# ftduino.net
KiCad netlist of a schematic drawn in EAGLE
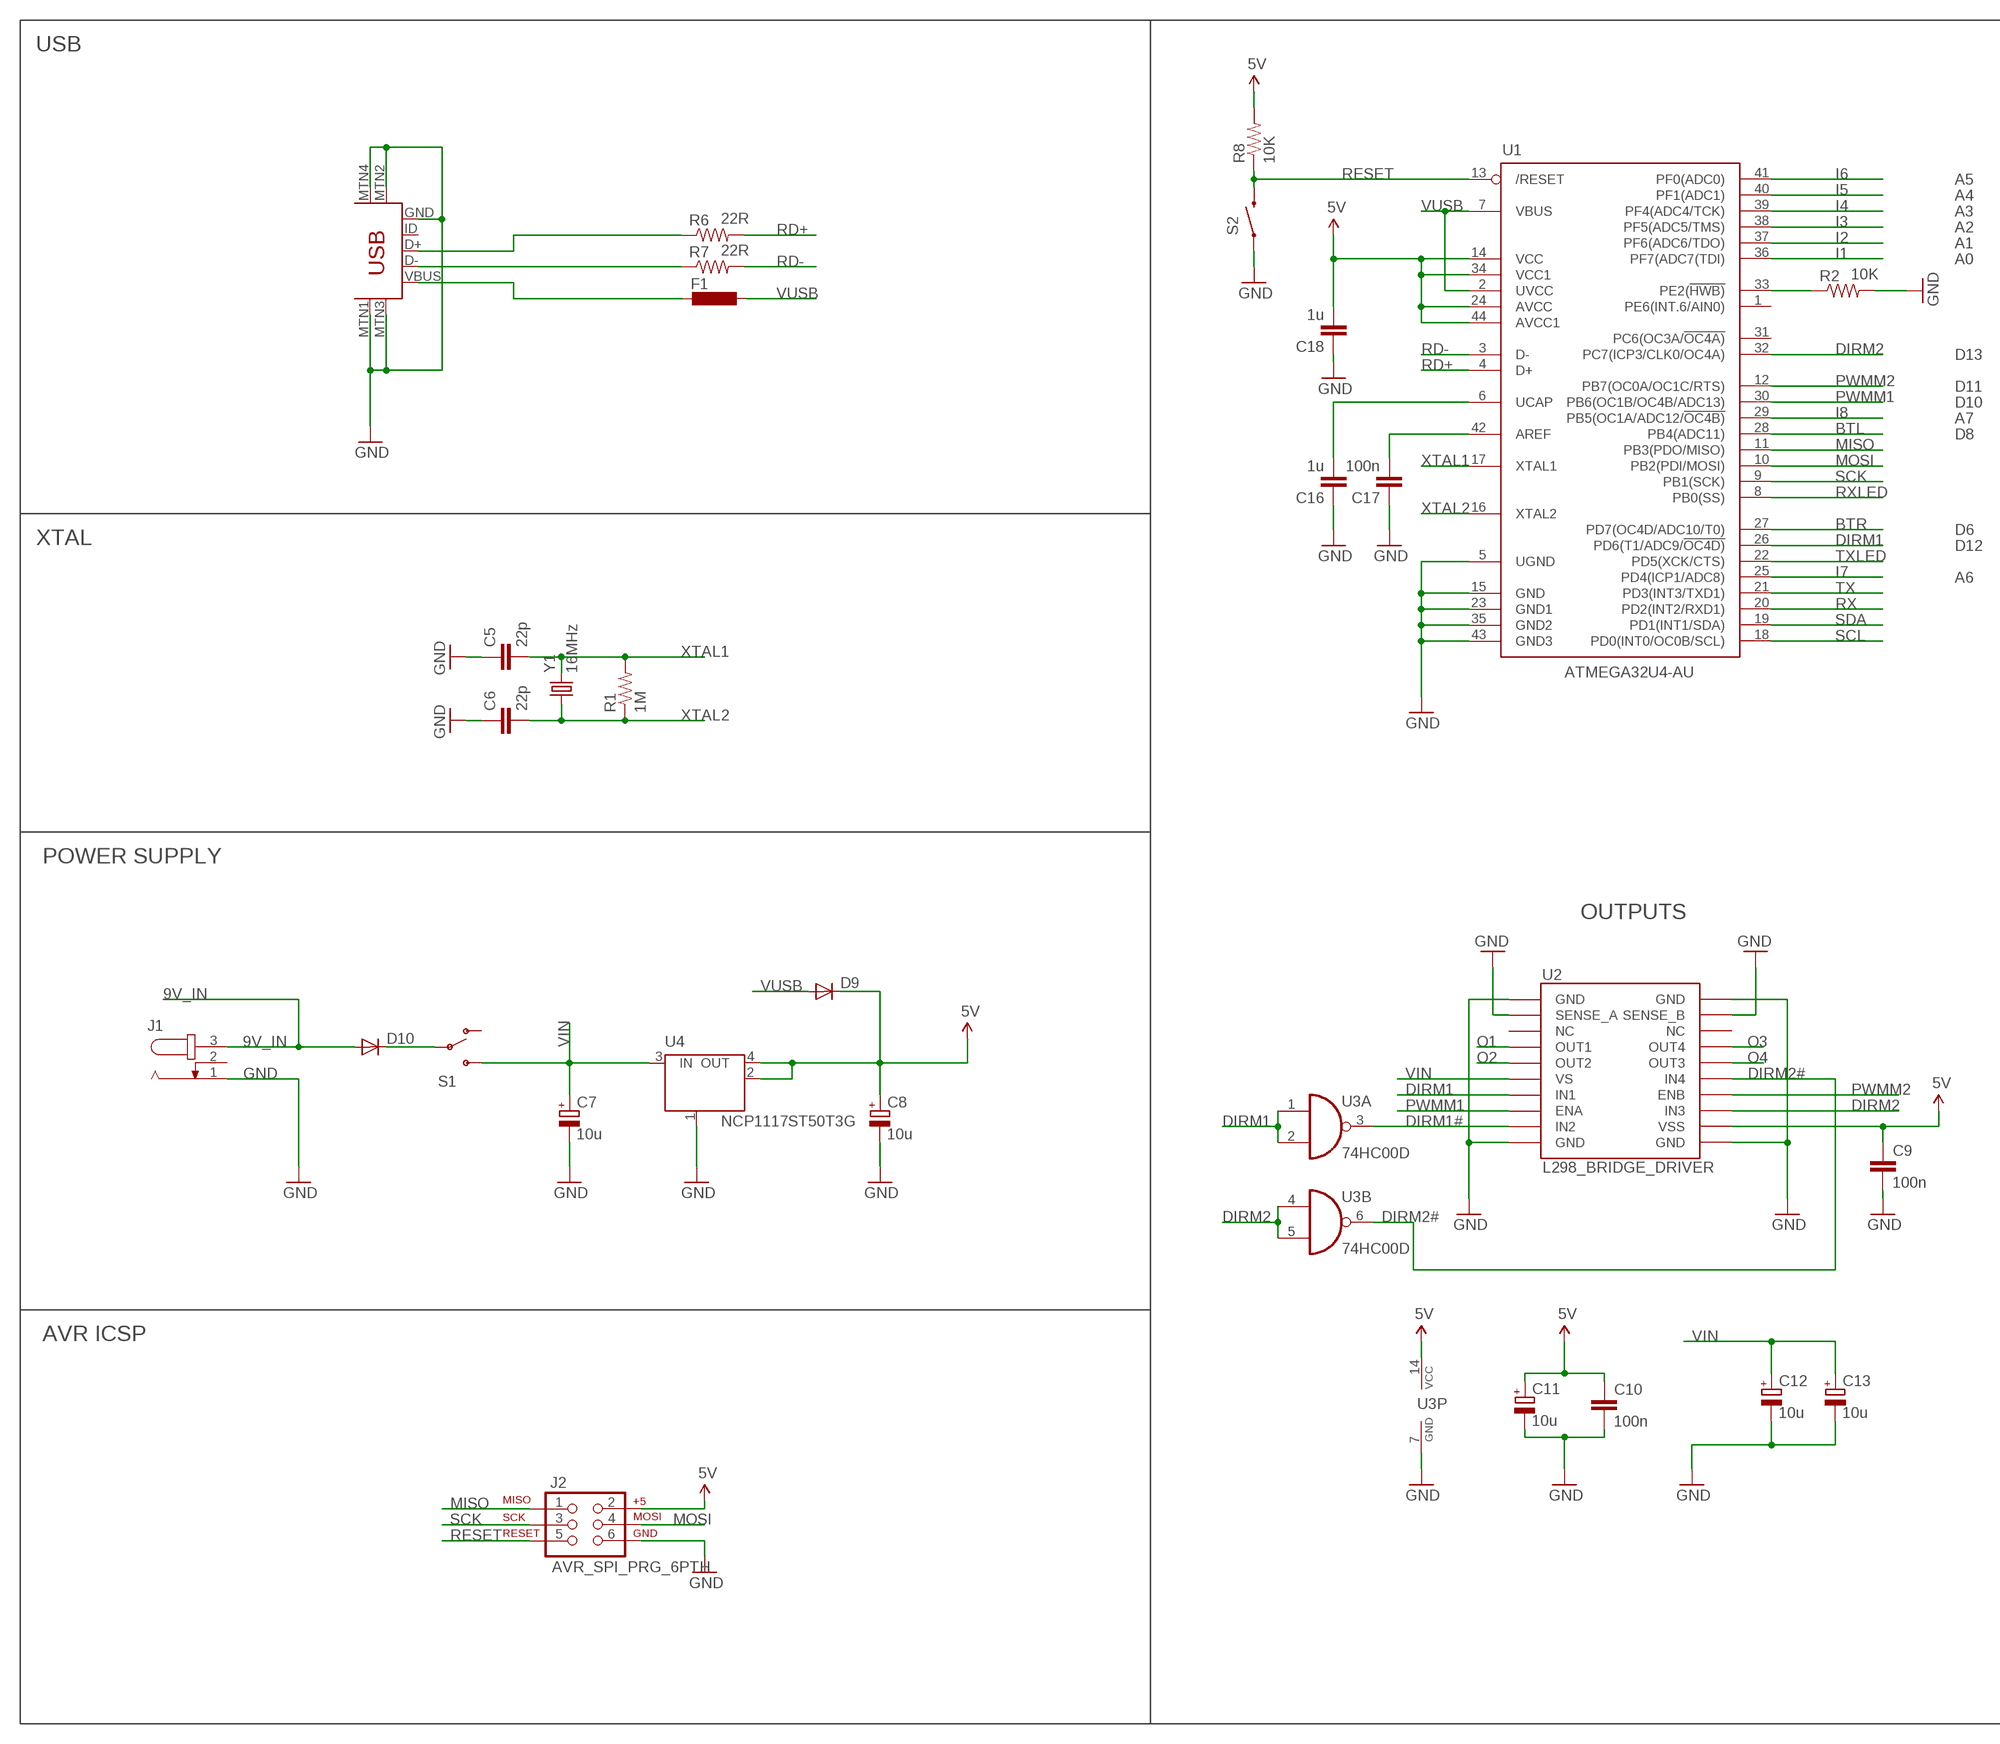
[diagram p0: schematic, sheet 1, part 1 of 2]
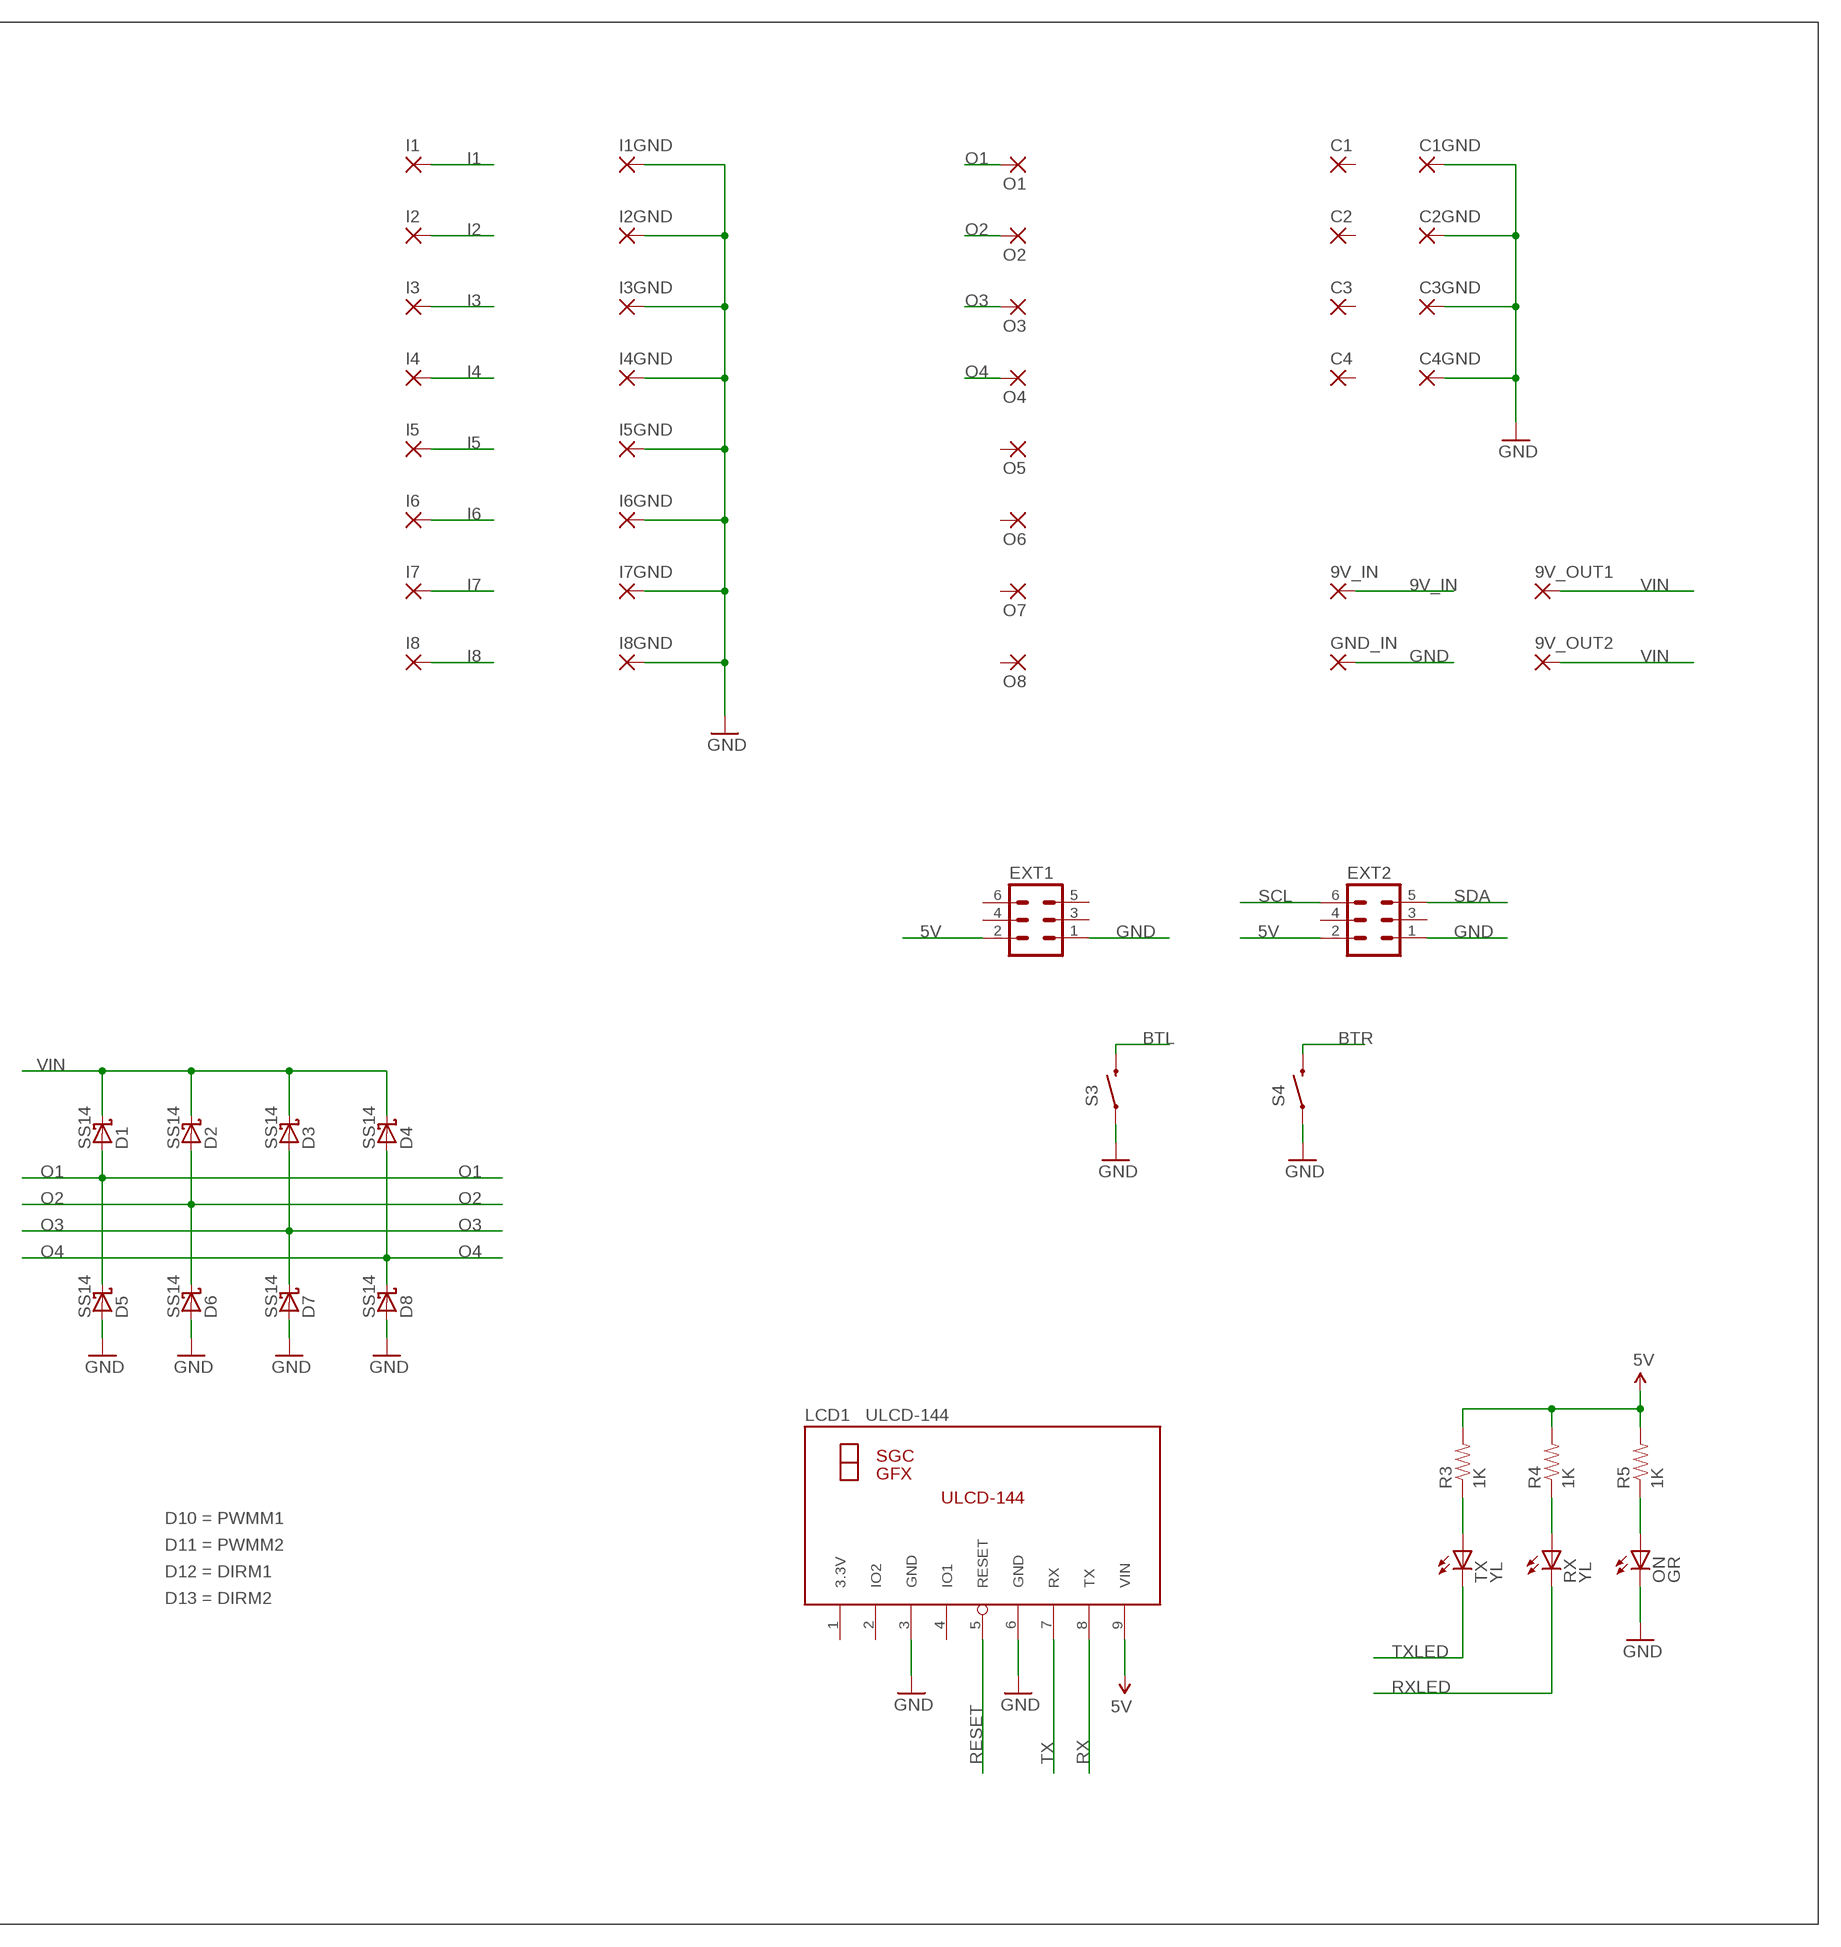
[diagram p1: schematic, sheet 1, part 2 of 2]

(export (version "E")
  (design (tool "Eeschema 10.0.6"))
  (components
    (comp (ref "9V_IN")
      (value "5,0/3,2")
      (footprint "eagle-import:5,0_3,2")
      (libsource (lib "eagle-import") (part "5,0/3,2"))
    )
    (comp (ref "9V_OUT1")
      (value "5,0/3,2")
      (footprint "eagle-import:5,0_3,2")
      (libsource (lib "eagle-import") (part "5,0/3,2"))
    )
    (comp (ref "9V_OUT2")
      (value "5,0/3,2")
      (footprint "eagle-import:5,0_3,2")
      (libsource (lib "eagle-import") (part "5,0/3,2"))
    )
    (comp (ref "C1")
      (value "5,0/3,2")
      (footprint "eagle-import:5,0_3,2")
      (libsource (lib "eagle-import") (part "5,0/3,2"))
    )
    (comp (ref "C1GND")
      (value "5,0/3,2")
      (footprint "eagle-import:5,0_3,2")
      (libsource (lib "eagle-import") (part "5,0/3,2"))
    )
    (comp (ref "C2")
      (value "5,0/3,2")
      (footprint "eagle-import:5,0_3,2")
      (libsource (lib "eagle-import") (part "5,0/3,2"))
    )
    (comp (ref "C2GND")
      (value "5,0/3,2")
      (footprint "eagle-import:5,0_3,2")
      (libsource (lib "eagle-import") (part "5,0/3,2"))
    )
    (comp (ref "C3")
      (value "5,0/3,2")
      (footprint "eagle-import:5,0_3,2")
      (libsource (lib "eagle-import") (part "5,0/3,2"))
    )
    (comp (ref "C3GND")
      (value "5,0/3,2")
      (footprint "eagle-import:5,0_3,2")
      (libsource (lib "eagle-import") (part "5,0/3,2"))
    )
    (comp (ref "C4")
      (value "5,0/3,2")
      (footprint "eagle-import:5,0_3,2")
      (libsource (lib "eagle-import") (part "5,0/3,2"))
    )
    (comp (ref "C4GND")
      (value "5,0/3,2")
      (footprint "eagle-import:5,0_3,2")
      (libsource (lib "eagle-import") (part "5,0/3,2"))
    )
    (comp (ref "C5")
      (value "22p")
      (footprint "eagle-import:0603-CAP")
      (libsource (lib "eagle-import") (part "CAP0603-CAP"))
    )
    (comp (ref "C6")
      (value "22p")
      (footprint "eagle-import:0603-CAP")
      (libsource (lib "eagle-import") (part "CAP0603-CAP"))
    )
    (comp (ref "C7")
      (value "10u")
      (footprint "eagle-import:SMC_B")
      (libsource (lib "eagle-import") (part "CPOL-EUSMCB"))
    )
    (comp (ref "C8")
      (value "10u")
      (footprint "eagle-import:SMC_B")
      (libsource (lib "eagle-import") (part "CPOL-EUSMCB"))
    )
    (comp (ref "C9")
      (value "100n")
      (footprint "eagle-import:0603-CAP")
      (libsource (lib "eagle-import") (part "CAP0603-CAP"))
    )
    (comp (ref "C10")
      (value "100n")
      (footprint "eagle-import:0603-CAP")
      (libsource (lib "eagle-import") (part "CAP0603-CAP"))
    )
    (comp (ref "C11")
      (value "10u")
      (footprint "eagle-import:SMC_B")
      (libsource (lib "eagle-import") (part "CPOL-EUSMCB"))
    )
    (comp (ref "C12")
      (value "10u")
      (footprint "eagle-import:SMC_B")
      (libsource (lib "eagle-import") (part "CPOL-EUSMCB"))
    )
    (comp (ref "C13")
      (value "10u")
      (footprint "eagle-import:SMC_B")
      (libsource (lib "eagle-import") (part "CPOL-EUSMCB"))
    )
    (comp (ref "C16")
      (value "1u")
      (footprint "eagle-import:0603-CAP")
      (libsource (lib "eagle-import") (part "CAP0603-CAP"))
    )
    (comp (ref "C17")
      (value "100n")
      (footprint "eagle-import:0603-CAP")
      (libsource (lib "eagle-import") (part "CAP0603-CAP"))
    )
    (comp (ref "C18")
      (value "1u")
      (footprint "eagle-import:0603-CAP")
      (libsource (lib "eagle-import") (part "CAP0603-CAP"))
    )
    (comp (ref "D1")
      (value "SS14")
      (footprint "eagle-import:SMA")
      (libsource (lib "eagle-import") (part "SCHOTTKY-DIODE"))
    )
    (comp (ref "D2")
      (value "SS14")
      (footprint "eagle-import:SMA")
      (libsource (lib "eagle-import") (part "SCHOTTKY-DIODE"))
    )
    (comp (ref "D3")
      (value "SS14")
      (footprint "eagle-import:SMA")
      (libsource (lib "eagle-import") (part "SCHOTTKY-DIODE"))
    )
    (comp (ref "D4")
      (value "SS14")
      (footprint "eagle-import:SMA")
      (libsource (lib "eagle-import") (part "SCHOTTKY-DIODE"))
    )
    (comp (ref "D5")
      (value "SS14")
      (footprint "eagle-import:SMA")
      (libsource (lib "eagle-import") (part "SCHOTTKY-DIODE"))
    )
    (comp (ref "D6")
      (value "SS14")
      (footprint "eagle-import:SMA")
      (libsource (lib "eagle-import") (part "SCHOTTKY-DIODE"))
    )
    (comp (ref "D7")
      (value "SS14")
      (footprint "eagle-import:SMA")
      (libsource (lib "eagle-import") (part "SCHOTTKY-DIODE"))
    )
    (comp (ref "D8")
      (value "SS14")
      (footprint "eagle-import:SMA")
      (libsource (lib "eagle-import") (part "SCHOTTKY-DIODE"))
    )
    (comp (ref "D9")
      (value "DIODE-SMB")
      (footprint "eagle-import:SMB")
      (libsource (lib "eagle-import") (part "DIODE-SMB"))
    )
    (comp (ref "D10")
      (value "DIODE-SMB")
      (footprint "eagle-import:SMB")
      (libsource (lib "eagle-import") (part "DIODE-SMB"))
    )
    (comp (ref "EXT1")
      (value "MA03-2")
      (footprint "eagle-import:MA03-2")
      (libsource (lib "eagle-import") (part "MA03-2"))
    )
    (comp (ref "EXT2")
      (value "MA03-2")
      (footprint "eagle-import:MA03-2")
      (libsource (lib "eagle-import") (part "MA03-2"))
    )
    (comp (ref "F1")
      (value "L-EUL1812")
      (footprint "eagle-import:L1812")
      (libsource (lib "eagle-import") (part "L-EUL1812"))
    )
    (comp (ref "GND_IN")
      (value "5,0/3,2")
      (footprint "eagle-import:5,0_3,2")
      (libsource (lib "eagle-import") (part "5,0/3,2"))
    )
    (comp (ref "I1")
      (value "5,0/3,2")
      (footprint "eagle-import:5,0_3,2")
      (libsource (lib "eagle-import") (part "5,0/3,2"))
    )
    (comp (ref "I1GND")
      (value "5,0/3,2")
      (footprint "eagle-import:5,0_3,2")
      (libsource (lib "eagle-import") (part "5,0/3,2"))
    )
    (comp (ref "I2")
      (value "5,0/3,2")
      (footprint "eagle-import:5,0_3,2")
      (libsource (lib "eagle-import") (part "5,0/3,2"))
    )
    (comp (ref "I2GND")
      (value "5,0/3,2")
      (footprint "eagle-import:5,0_3,2")
      (libsource (lib "eagle-import") (part "5,0/3,2"))
    )
    (comp (ref "I3")
      (value "5,0/3,2")
      (footprint "eagle-import:5,0_3,2")
      (libsource (lib "eagle-import") (part "5,0/3,2"))
    )
    (comp (ref "I3GND")
      (value "5,0/3,2")
      (footprint "eagle-import:5,0_3,2")
      (libsource (lib "eagle-import") (part "5,0/3,2"))
    )
    (comp (ref "I4")
      (value "5,0/3,2")
      (footprint "eagle-import:5,0_3,2")
      (libsource (lib "eagle-import") (part "5,0/3,2"))
    )
    (comp (ref "I4GND")
      (value "5,0/3,2")
      (footprint "eagle-import:5,0_3,2")
      (libsource (lib "eagle-import") (part "5,0/3,2"))
    )
    (comp (ref "I5")
      (value "5,0/3,2")
      (footprint "eagle-import:5,0_3,2")
      (libsource (lib "eagle-import") (part "5,0/3,2"))
    )
    (comp (ref "I5GND")
      (value "5,0/3,2")
      (footprint "eagle-import:5,0_3,2")
      (libsource (lib "eagle-import") (part "5,0/3,2"))
    )
    (comp (ref "I6")
      (value "5,0/3,2")
      (footprint "eagle-import:5,0_3,2")
      (libsource (lib "eagle-import") (part "5,0/3,2"))
    )
    (comp (ref "I6GND")
      (value "5,0/3,2")
      (footprint "eagle-import:5,0_3,2")
      (libsource (lib "eagle-import") (part "5,0/3,2"))
    )
    (comp (ref "I7")
      (value "5,0/3,2")
      (footprint "eagle-import:5,0_3,2")
      (libsource (lib "eagle-import") (part "5,0/3,2"))
    )
    (comp (ref "I7GND")
      (value "5,0/3,2")
      (footprint "eagle-import:5,0_3,2")
      (libsource (lib "eagle-import") (part "5,0/3,2"))
    )
    (comp (ref "I8")
      (value "5,0/3,2")
      (footprint "eagle-import:5,0_3,2")
      (libsource (lib "eagle-import") (part "5,0/3,2"))
    )
    (comp (ref "I8GND")
      (value "5,0/3,2")
      (footprint "eagle-import:5,0_3,2")
      (libsource (lib "eagle-import") (part "5,0/3,2"))
    )
    (comp (ref "J1")
      (value "JACK-PLUG1")
      (footprint "eagle-import:JK3.5_1.8")
      (libsource (lib "eagle-import") (part "JACK-PLUG1"))
    )
    (comp (ref "J2")
      (value "AVR_SPI_PRG_6PTH")
      (footprint "eagle-import:2X3")
      (libsource (lib "eagle-import") (part "AVR_SPI_PRG_6PTH"))
    )
    (comp (ref "LCD1")
      (value "ULCD-144")
      (footprint "eagle-import:ULCD-144")
      (libsource (lib "eagle-import") (part "ULCD-144"))
    )
    (comp (ref "O1")
      (value "5,0/3,2")
      (footprint "eagle-import:5,0_3,2")
      (libsource (lib "eagle-import") (part "5,0/3,2"))
    )
    (comp (ref "O2")
      (value "5,0/3,2")
      (footprint "eagle-import:5,0_3,2")
      (libsource (lib "eagle-import") (part "5,0/3,2"))
    )
    (comp (ref "O3")
      (value "5,0/3,2")
      (footprint "eagle-import:5,0_3,2")
      (libsource (lib "eagle-import") (part "5,0/3,2"))
    )
    (comp (ref "O4")
      (value "5,0/3,2")
      (footprint "eagle-import:5,0_3,2")
      (libsource (lib "eagle-import") (part "5,0/3,2"))
    )
    (comp (ref "O5")
      (value "5,0/3,2")
      (footprint "eagle-import:5,0_3,2")
      (libsource (lib "eagle-import") (part "5,0/3,2"))
    )
    (comp (ref "O6")
      (value "5,0/3,2")
      (footprint "eagle-import:5,0_3,2")
      (libsource (lib "eagle-import") (part "5,0/3,2"))
    )
    (comp (ref "O7")
      (value "5,0/3,2")
      (footprint "eagle-import:5,0_3,2")
      (libsource (lib "eagle-import") (part "5,0/3,2"))
    )
    (comp (ref "O8")
      (value "5,0/3,2")
      (footprint "eagle-import:5,0_3,2")
      (libsource (lib "eagle-import") (part "5,0/3,2"))
    )
    (comp (ref "ON")
      (value "GR")
      (footprint "eagle-import:CHIPLED_0805")
      (libsource (lib "eagle-import") (part "LEDCHIPLED_0805"))
    )
    (comp (ref "R1")
      (value "1M")
      (footprint "eagle-import:0603-RES")
      (libsource (lib "eagle-import") (part "RESISTOR0603-RES"))
    )
    (comp (ref "R2")
      (value "10K")
      (footprint "eagle-import:0603-RES")
      (libsource (lib "eagle-import") (part "RESISTOR0603-RES"))
    )
    (comp (ref "R3")
      (value "1K")
      (footprint "eagle-import:0603-RES")
      (libsource (lib "eagle-import") (part "RESISTOR0603-RES"))
    )
    (comp (ref "R4")
      (value "1K")
      (footprint "eagle-import:0603-RES")
      (libsource (lib "eagle-import") (part "RESISTOR0603-RES"))
    )
    (comp (ref "R5")
      (value "1K")
      (footprint "eagle-import:0603-RES")
      (libsource (lib "eagle-import") (part "RESISTOR0603-RES"))
    )
    (comp (ref "R6")
      (value "22R")
      (footprint "eagle-import:0603-RES")
      (libsource (lib "eagle-import") (part "RESISTOR0603-RES"))
    )
    (comp (ref "R7")
      (value "22R")
      (footprint "eagle-import:0603-RES")
      (libsource (lib "eagle-import") (part "RESISTOR0603-RES"))
    )
    (comp (ref "R8")
      (value "10K")
      (footprint "eagle-import:0603-RES")
      (libsource (lib "eagle-import") (part "RESISTOR0603-RES"))
    )
    (comp (ref "RX")
      (value "YL")
      (footprint "eagle-import:CHIPLED_0805")
      (libsource (lib "eagle-import") (part "LEDCHIPLED_0805"))
    )
    (comp (ref "S1")
      (value "SWITCH-SPSTPTH")
      (footprint "eagle-import:SWITCH-SPDT")
      (libsource (lib "eagle-import") (part "SWITCH-SPSTPTH"))
    )
    (comp (ref "S2")
      (value "SWITCH-MOMENTARY-2PTH")
      (footprint "eagle-import:TACTILE-PTH")
      (libsource (lib "eagle-import") (part "SWITCH-MOMENTARY-2PTH"))
    )
    (comp (ref "S3")
      (value "SWITCH-MOMENTARY-2PTH")
      (footprint "eagle-import:TACTILE-PTH")
      (libsource (lib "eagle-import") (part "SWITCH-MOMENTARY-2PTH"))
    )
    (comp (ref "S4")
      (value "SWITCH-MOMENTARY-2PTH")
      (footprint "eagle-import:TACTILE-PTH")
      (libsource (lib "eagle-import") (part "SWITCH-MOMENTARY-2PTH"))
    )
    (comp (ref "TX")
      (value "YL")
      (footprint "eagle-import:CHIPLED_0805")
      (libsource (lib "eagle-import") (part "LEDCHIPLED_0805"))
    )
    (comp (ref "U1")
      (value "ATMEGA32U4-AU")
      (footprint "eagle-import:TQFP44")
      (libsource (lib "eagle-import") (part "ATMEGA32U4-AU"))
    )
    (comp (ref "U2")
      (value "L298_BRIDGE_DRIVER")
      (footprint "eagle-import:POWERSO20")
      (libsource (lib "eagle-import") (part "L298_BRIDGE_DRIVER"))
    )
    (comp (ref "U3")
      (value "74HC00D")
      (footprint "eagle-import:SO14")
      (libsource (lib "eagle-import") (part "7400DHC"))
    )
    (comp (ref "U4")
      (value "NCP1117ST50T3G")
      (footprint "eagle-import:SOT223")
      (libsource (lib "eagle-import") (part "MC33269ST-3.3T3"))
    )
    (comp (ref "X1")
      (value "USB-MINIB-5PIN")
      (footprint "eagle-import:USB-MINIB")
      (libsource (lib "eagle-import") (part "USB-MINIB-5PIN"))
    )
    (comp (ref "Y1")
      (value "16MHz")
      (footprint "eagle-import:CTS406")
      (libsource (lib "eagle-import") (part "CRYSTALCTS406"))
    )
  )
  (nets
    (net (code "1") (name "/3.3V") (class "Default")
      (node (ref "LCD1") (pin "1") (pinfunction "3.3V_1") (pintype "power_in"))
    )
    (net (code "2") (name "/9V_IN") (class "Default")
      (node (ref "9V_IN") (pin "1") (pinfunction "P_1") (pintype "passive"))
      (node (ref "D10") (pin "A") (pinfunction "A_A") (pintype "passive"))
      (node (ref "J1") (pin "3") (pinfunction "3_3") (pintype "passive"))
    )
    (net (code "3") (name "/BTL") (class "Default")
      (node (ref "S3") (pin "3") (pinfunction "2_3") (pintype "passive"))
      (node (ref "U1") (pin "28") (pinfunction "PB4(ADC11)_28") (pintype "bidirectional"))
    )
    (net (code "4") (name "/BTR") (class "Default")
      (node (ref "S4") (pin "3") (pinfunction "2_3") (pintype "passive"))
      (node (ref "U1") (pin "27") (pinfunction "PD7(OC4D/ADC10/T0)_27") (pintype "bidirectional"))
    )
    (net (code "5") (name "/DIRM1") (class "Default")
      (node (ref "U1") (pin "26") (pinfunction "PD6(T1/ADC9/~{OC4D})_26") (pintype "bidirectional"))
      (node (ref "U2") (pin "7") (pinfunction "IN1_7") (pintype "bidirectional"))
      (node (ref "U3") (pin "1") (pinfunction "I0_1") (pintype "input"))
      (node (ref "U3") (pin "2") (pinfunction "I1_2") (pintype "input"))
    )
    (net (code "6") (name "/DIRM1#") (class "Default")
      (node (ref "U2") (pin "9") (pinfunction "IN2_9") (pintype "bidirectional"))
      (node (ref "U3") (pin "3") (pinfunction "O_3") (pintype "output"))
    )
    (net (code "7") (name "/DIRM2") (class "Default")
      (node (ref "U1") (pin "32") (pinfunction "PC7(ICP3/CLK0/OC4A)_32") (pintype "bidirectional"))
      (node (ref "U2") (pin "13") (pinfunction "IN3_13") (pintype "bidirectional"))
      (node (ref "U3") (pin "4") (pinfunction "I0_4") (pintype "input"))
      (node (ref "U3") (pin "5") (pinfunction "I1_5") (pintype "input"))
    )
    (net (code "8") (name "/DIRM2#") (class "Default")
      (node (ref "U2") (pin "15") (pinfunction "IN4_15") (pintype "bidirectional"))
      (node (ref "U3") (pin "6") (pinfunction "O_6") (pintype "output"))
    )
    (net (code "9") (name "/I1") (class "Default")
      (node (ref "I1") (pin "1") (pinfunction "P_1") (pintype "passive"))
      (node (ref "U1") (pin "36") (pinfunction "PF7(ADC7(TDI)_36") (pintype "bidirectional"))
    )
    (net (code "10") (name "/I2") (class "Default")
      (node (ref "I2") (pin "1") (pinfunction "P_1") (pintype "passive"))
      (node (ref "U1") (pin "37") (pinfunction "PF6(ADC6/TDO)_37") (pintype "bidirectional"))
    )
    (net (code "11") (name "/I3") (class "Default")
      (node (ref "I3") (pin "1") (pinfunction "P_1") (pintype "passive"))
      (node (ref "U1") (pin "38") (pinfunction "PF5(ADC5/TMS)_38") (pintype "bidirectional"))
    )
    (net (code "12") (name "/I4") (class "Default")
      (node (ref "I4") (pin "1") (pinfunction "P_1") (pintype "passive"))
      (node (ref "U1") (pin "39") (pinfunction "PF4(ADC4/TCK)_39") (pintype "bidirectional"))
    )
    (net (code "13") (name "/I5") (class "Default")
      (node (ref "I5") (pin "1") (pinfunction "P_1") (pintype "passive"))
      (node (ref "U1") (pin "40") (pinfunction "PF1(ADC1)_40") (pintype "bidirectional"))
    )
    (net (code "14") (name "/I6") (class "Default")
      (node (ref "I6") (pin "1") (pinfunction "P_1") (pintype "passive"))
      (node (ref "U1") (pin "41") (pinfunction "PF0(ADC0)_41") (pintype "bidirectional"))
    )
    (net (code "15") (name "/I7") (class "Default")
      (node (ref "I7") (pin "1") (pinfunction "P_1") (pintype "passive"))
      (node (ref "U1") (pin "25") (pinfunction "PD4(ICP1/ADC8)_25") (pintype "bidirectional"))
    )
    (net (code "16") (name "/I8") (class "Default")
      (node (ref "I8") (pin "1") (pinfunction "P_1") (pintype "passive"))
      (node (ref "U1") (pin "29") (pinfunction "PB5(OC1A/ADC12/~{OC4B})_29") (pintype "bidirectional"))
    )
    (net (code "17") (name "/MISO") (class "Default")
      (node (ref "J2") (pin "1") (pinfunction "1_1") (pintype "passive"))
      (node (ref "U1") (pin "11") (pinfunction "PB3(PDO/MISO)_11") (pintype "bidirectional"))
    )
    (net (code "18") (name "/MOSI") (class "Default")
      (node (ref "J2") (pin "4") (pinfunction "4_4") (pintype "passive"))
      (node (ref "U1") (pin "10") (pinfunction "PB2(PDI/MOSI)_10") (pintype "bidirectional"))
    )
    (net (code "19") (name "/O1") (class "Default")
      (node (ref "D1") (pin "A") (pinfunction "A_A") (pintype "passive"))
      (node (ref "D5") (pin "C") (pinfunction "C_C") (pintype "passive"))
      (node (ref "O1") (pin "1") (pinfunction "P_1") (pintype "passive"))
      (node (ref "U2") (pin "4") (pinfunction "OUT1_4") (pintype "bidirectional"))
    )
    (net (code "20") (name "/O2") (class "Default")
      (node (ref "D2") (pin "A") (pinfunction "A_A") (pintype "passive"))
      (node (ref "D6") (pin "C") (pinfunction "C_C") (pintype "passive"))
      (node (ref "O2") (pin "1") (pinfunction "P_1") (pintype "passive"))
      (node (ref "U2") (pin "5") (pinfunction "OUT2_5") (pintype "bidirectional"))
    )
    (net (code "21") (name "/O3") (class "Default")
      (node (ref "D3") (pin "A") (pinfunction "A_A") (pintype "passive"))
      (node (ref "D7") (pin "C") (pinfunction "C_C") (pintype "passive"))
      (node (ref "O3") (pin "1") (pinfunction "P_1") (pintype "passive"))
      (node (ref "U2") (pin "17") (pinfunction "OUT4_17") (pintype "bidirectional"))
    )
    (net (code "22") (name "/O4") (class "Default")
      (node (ref "D4") (pin "A") (pinfunction "A_A") (pintype "passive"))
      (node (ref "D8") (pin "C") (pinfunction "C_C") (pintype "passive"))
      (node (ref "O4") (pin "1") (pinfunction "P_1") (pintype "passive"))
      (node (ref "U2") (pin "16") (pinfunction "OUT3_16") (pintype "bidirectional"))
    )
    (net (code "23") (name "/PWMM1") (class "Default")
      (node (ref "U1") (pin "30") (pinfunction "PB6(OC1B/OC4B/ADC13)_30") (pintype "bidirectional"))
      (node (ref "U2") (pin "8") (pinfunction "ENA_8") (pintype "bidirectional"))
    )
    (net (code "24") (name "/PWMM2") (class "Default")
      (node (ref "U1") (pin "12") (pinfunction "PB7(OC0A/OC1C/RTS)_12") (pintype "bidirectional"))
      (node (ref "U2") (pin "14") (pinfunction "ENB_14") (pintype "bidirectional"))
    )
    (net (code "25") (name "/RD+") (class "Default")
      (node (ref "R6") (pin "2") (pinfunction "2_2") (pintype "passive"))
      (node (ref "U1") (pin "4") (pinfunction "D+_4") (pintype "bidirectional"))
    )
    (net (code "26") (name "/RD-") (class "Default")
      (node (ref "R7") (pin "2") (pinfunction "2_2") (pintype "passive"))
      (node (ref "U1") (pin "3") (pinfunction "D-_3") (pintype "bidirectional"))
    )
    (net (code "27") (name "/RESET") (class "Default")
      (node (ref "J2") (pin "5") (pinfunction "5_5") (pintype "passive"))
      (node (ref "LCD1") (pin "5") (pinfunction "RESET_5") (pintype "input"))
      (node (ref "R8") (pin "1") (pinfunction "1_1") (pintype "passive"))
      (node (ref "S2") (pin "3") (pinfunction "2_3") (pintype "passive"))
      (node (ref "U1") (pin "13") (pinfunction "/RESET_13") (pintype "bidirectional"))
    )
    (net (code "28") (name "/RX") (class "Default")
      (node (ref "LCD1") (pin "8") (pinfunction "TX_8") (pintype "output"))
      (node (ref "U1") (pin "20") (pinfunction "PD2(INT2/RXD1)_20") (pintype "bidirectional"))
    )
    (net (code "29") (name "/RXLED") (class "Default")
      (node (ref "RX") (pin "C") (pinfunction "C_C") (pintype "passive"))
      (node (ref "U1") (pin "8") (pinfunction "PB0(SS)_8") (pintype "bidirectional"))
    )
    (net (code "30") (name "/SCK") (class "Default")
      (node (ref "J2") (pin "3") (pinfunction "3_3") (pintype "passive"))
      (node (ref "U1") (pin "9") (pinfunction "PB1(SCK)_9") (pintype "bidirectional"))
    )
    (net (code "31") (name "/SCL") (class "Default")
      (node (ref "EXT2") (pin "6") (pinfunction "6_6") (pintype "passive"))
      (node (ref "U1") (pin "18") (pinfunction "PD0(INT0/OC0B/SCL)_18") (pintype "bidirectional"))
    )
    (net (code "32") (name "/SDA") (class "Default")
      (node (ref "EXT2") (pin "5") (pinfunction "5_5") (pintype "passive"))
      (node (ref "U1") (pin "19") (pinfunction "PD1(INT1/SDA)_19") (pintype "bidirectional"))
    )
    (net (code "33") (name "/TX") (class "Default")
      (node (ref "LCD1") (pin "7") (pinfunction "RX_7") (pintype "input"))
      (node (ref "U1") (pin "21") (pinfunction "PD3(INT3/TXD1)_21") (pintype "bidirectional"))
    )
    (net (code "34") (name "/TXLED") (class "Default")
      (node (ref "TX") (pin "C") (pinfunction "C_C") (pintype "passive"))
      (node (ref "U1") (pin "22") (pinfunction "PD5(XCK/CTS)_22") (pintype "bidirectional"))
    )
    (net (code "35") (name "/VIN") (class "Default")
      (node (ref "9V_OUT1") (pin "1") (pinfunction "P_1") (pintype "passive"))
      (node (ref "9V_OUT2") (pin "1") (pinfunction "P_1") (pintype "passive"))
      (node (ref "C12") (pin "+") (pinfunction "+_+") (pintype "passive"))
      (node (ref "C13") (pin "+") (pinfunction "+_+") (pintype "passive"))
      (node (ref "C7") (pin "+") (pinfunction "+_+") (pintype "passive"))
      (node (ref "D1") (pin "C") (pinfunction "C_C") (pintype "passive"))
      (node (ref "D2") (pin "C") (pinfunction "C_C") (pintype "passive"))
      (node (ref "D3") (pin "C") (pinfunction "C_C") (pintype "passive"))
      (node (ref "D4") (pin "C") (pinfunction "C_C") (pintype "passive"))
      (node (ref "S1") (pin "3") (pinfunction "S_3") (pintype "passive"))
      (node (ref "U2") (pin "6") (pinfunction "VS_6") (pintype "bidirectional"))
      (node (ref "U4") (pin "3") (pinfunction "IN_3") (pintype "input"))
    )
    (net (code "36") (name "/VUSB") (class "Default")
      (node (ref "D9") (pin "A") (pinfunction "A_A") (pintype "passive"))
      (node (ref "F1") (pin "1") (pinfunction "1_1") (pintype "passive"))
      (node (ref "U1") (pin "2") (pinfunction "UVCC_2") (pintype "bidirectional"))
      (node (ref "U1") (pin "7") (pinfunction "VBUS_7") (pintype "bidirectional"))
    )
    (net (code "37") (name "/XTAL1") (class "Default")
      (node (ref "C5") (pin "2") (pinfunction "2_2") (pintype "passive"))
      (node (ref "R1") (pin "2") (pinfunction "2_2") (pintype "passive"))
      (node (ref "U1") (pin "17") (pinfunction "XTAL1_17") (pintype "bidirectional"))
      (node (ref "Y1") (pin "3") (pinfunction "2_3") (pintype "passive"))
    )
    (net (code "38") (name "/XTAL2") (class "Default")
      (node (ref "C6") (pin "2") (pinfunction "2_2") (pintype "passive"))
      (node (ref "R1") (pin "1") (pinfunction "1_1") (pintype "passive"))
      (node (ref "U1") (pin "16") (pinfunction "XTAL2_16") (pintype "bidirectional"))
      (node (ref "Y1") (pin "1") (pinfunction "1_1") (pintype "passive"))
    )
    (net (code "39") (name "5V") (class "Default")
      (node (ref "C10") (pin "1") (pinfunction "1_1") (pintype "passive"))
      (node (ref "C11") (pin "+") (pinfunction "+_+") (pintype "passive"))
      (node (ref "C18") (pin "2") (pinfunction "2_2") (pintype "passive"))
      (node (ref "C8") (pin "+") (pinfunction "+_+") (pintype "passive"))
      (node (ref "C9") (pin "1") (pinfunction "1_1") (pintype "passive"))
      (node (ref "D9") (pin "C") (pinfunction "C_C") (pintype "passive"))
      (node (ref "EXT1") (pin "2") (pinfunction "2_2") (pintype "passive"))
      (node (ref "EXT2") (pin "2") (pinfunction "2_2") (pintype "passive"))
      (node (ref "J2") (pin "2") (pinfunction "2_2") (pintype "passive"))
      (node (ref "LCD1") (pin "9") (pinfunction "VIN_9") (pintype "power_in"))
      (node (ref "R3") (pin "2") (pinfunction "2_2") (pintype "passive"))
      (node (ref "R4") (pin "2") (pinfunction "2_2") (pintype "passive"))
      (node (ref "R5") (pin "2") (pinfunction "2_2") (pintype "passive"))
      (node (ref "R8") (pin "2") (pinfunction "2_2") (pintype "passive"))
      (node (ref "U1") (pin "14") (pinfunction "VCC_14") (pintype "bidirectional"))
      (node (ref "U1") (pin "24") (pinfunction "AVCC_24") (pintype "bidirectional"))
      (node (ref "U1") (pin "34") (pinfunction "VCC1_34") (pintype "bidirectional"))
      (node (ref "U1") (pin "44") (pinfunction "AVCC1_44") (pintype "bidirectional"))
      (node (ref "U2") (pin "12") (pinfunction "VSS_12") (pintype "bidirectional"))
      (node (ref "U3") (pin "14") (pinfunction "VCC_14") (pintype "power_in"))
      (node (ref "U4") (pin "2") (pinfunction "OUT_2") (pintype "passive"))
      (node (ref "U4") (pin "4") (pinfunction "OUT_4") (pintype "passive"))
    )
    (net (code "40") (name "GND") (class "Default")
      (node (ref "C10") (pin "2") (pinfunction "2_2") (pintype "passive"))
      (node (ref "C11") (pin "-") (pinfunction "-_-") (pintype "passive"))
      (node (ref "C12") (pin "-") (pinfunction "-_-") (pintype "passive"))
      (node (ref "C13") (pin "-") (pinfunction "-_-") (pintype "passive"))
      (node (ref "C16") (pin "1") (pinfunction "1_1") (pintype "passive"))
      (node (ref "C17") (pin "1") (pinfunction "1_1") (pintype "passive"))
      (node (ref "C18") (pin "1") (pinfunction "1_1") (pintype "passive"))
      (node (ref "C1GND") (pin "1") (pinfunction "P_1") (pintype "passive"))
      (node (ref "C2GND") (pin "1") (pinfunction "P_1") (pintype "passive"))
      (node (ref "C3GND") (pin "1") (pinfunction "P_1") (pintype "passive"))
      (node (ref "C4GND") (pin "1") (pinfunction "P_1") (pintype "passive"))
      (node (ref "C5") (pin "1") (pinfunction "1_1") (pintype "passive"))
      (node (ref "C6") (pin "1") (pinfunction "1_1") (pintype "passive"))
      (node (ref "C7") (pin "-") (pinfunction "-_-") (pintype "passive"))
      (node (ref "C8") (pin "-") (pinfunction "-_-") (pintype "passive"))
      (node (ref "C9") (pin "2") (pinfunction "2_2") (pintype "passive"))
      (node (ref "D5") (pin "A") (pinfunction "A_A") (pintype "passive"))
      (node (ref "D6") (pin "A") (pinfunction "A_A") (pintype "passive"))
      (node (ref "D7") (pin "A") (pinfunction "A_A") (pintype "passive"))
      (node (ref "D8") (pin "A") (pinfunction "A_A") (pintype "passive"))
      (node (ref "EXT1") (pin "1") (pinfunction "1_1") (pintype "passive"))
      (node (ref "EXT2") (pin "1") (pinfunction "1_1") (pintype "passive"))
      (node (ref "GND_IN") (pin "1") (pinfunction "P_1") (pintype "passive"))
      (node (ref "I1GND") (pin "1") (pinfunction "P_1") (pintype "passive"))
      (node (ref "I2GND") (pin "1") (pinfunction "P_1") (pintype "passive"))
      (node (ref "I3GND") (pin "1") (pinfunction "P_1") (pintype "passive"))
      (node (ref "I4GND") (pin "1") (pinfunction "P_1") (pintype "passive"))
      (node (ref "I5GND") (pin "1") (pinfunction "P_1") (pintype "passive"))
      (node (ref "I6GND") (pin "1") (pinfunction "P_1") (pintype "passive"))
      (node (ref "I7GND") (pin "1") (pinfunction "P_1") (pintype "passive"))
      (node (ref "I8GND") (pin "1") (pinfunction "P_1") (pintype "passive"))
      (node (ref "J1") (pin "1") (pinfunction "1_1") (pintype "passive"))
      (node (ref "J2") (pin "6") (pinfunction "6_6") (pintype "passive"))
      (node (ref "LCD1") (pin "3") (pinfunction "GND_3") (pintype "power_in"))
      (node (ref "LCD1") (pin "6") (pinfunction "GND_6") (pintype "bidirectional"))
      (node (ref "ON") (pin "C") (pinfunction "C_C") (pintype "passive"))
      (node (ref "R2") (pin "2") (pinfunction "2_2") (pintype "passive"))
      (node (ref "S2") (pin "1") (pinfunction "1_1") (pintype "passive"))
      (node (ref "S3") (pin "1") (pinfunction "1_1") (pintype "passive"))
      (node (ref "S4") (pin "1") (pinfunction "1_1") (pintype "passive"))
      (node (ref "U1") (pin "15") (pinfunction "GND_15") (pintype "bidirectional"))
      (node (ref "U1") (pin "23") (pinfunction "GND1_23") (pintype "bidirectional"))
      (node (ref "U1") (pin "35") (pinfunction "GND2_35") (pintype "bidirectional"))
      (node (ref "U1") (pin "43") (pinfunction "GND3_43") (pintype "bidirectional"))
      (node (ref "U1") (pin "5") (pinfunction "UGND_5") (pintype "bidirectional"))
      (node (ref "U2") (pin "1") (pinfunction "GND_1") (pintype "bidirectional"))
      (node (ref "U2") (pin "10") (pinfunction "GND_10") (pintype "bidirectional"))
      (node (ref "U2") (pin "11") (pinfunction "GND_11") (pintype "bidirectional"))
      (node (ref "U2") (pin "19") (pinfunction "SENSE_B_19") (pintype "bidirectional"))
      (node (ref "U2") (pin "2") (pinfunction "SENSE_A_2") (pintype "bidirectional"))
      (node (ref "U2") (pin "20") (pinfunction "GND_20") (pintype "bidirectional"))
      (node (ref "U3") (pin "7") (pinfunction "GND_7") (pintype "power_in"))
      (node (ref "U4") (pin "1") (pinfunction "GND/ADJ_1") (pintype "input"))
      (node (ref "X1") (pin "GND") (pinfunction "GND_GND") (pintype "bidirectional"))
      (node (ref "X1") (pin "MTN1") (pinfunction "MTN2_MTN1") (pintype "bidirectional"))
      (node (ref "X1") (pin "MTN2") (pinfunction "MTN3_MTN2") (pintype "bidirectional"))
      (node (ref "X1") (pin "MTN3") (pinfunction "MTN1_MTN3") (pintype "bidirectional"))
      (node (ref "X1") (pin "MTN4") (pinfunction "MTN4_MTN4") (pintype "bidirectional"))
    )
    (net (code "41") (name "Net-(F1-Pad2)") (class "Default")
      (node (ref "F1") (pin "2") (pinfunction "2_2") (pintype "passive"))
      (node (ref "X1") (pin "VBUS") (pinfunction "VBUS_VBUS") (pintype "bidirectional"))
    )
    (net (code "42") (name "Net-(ON-PadA)") (class "Default")
      (node (ref "ON") (pin "A") (pinfunction "A_A") (pintype "passive"))
      (node (ref "R5") (pin "1") (pinfunction "1_1") (pintype "passive"))
    )
    (net (code "43") (name "Net-(R3-Pad1)") (class "Default")
      (node (ref "R3") (pin "1") (pinfunction "1_1") (pintype "passive"))
      (node (ref "TX") (pin "A") (pinfunction "A_A") (pintype "passive"))
    )
    (net (code "44") (name "Net-(R4-Pad1)") (class "Default")
      (node (ref "R4") (pin "1") (pinfunction "1_1") (pintype "passive"))
      (node (ref "RX") (pin "A") (pinfunction "A_A") (pintype "passive"))
    )
    (net (code "45") (name "Net-(R6-Pad1)") (class "Default")
      (node (ref "R6") (pin "1") (pinfunction "1_1") (pintype "passive"))
      (node (ref "X1") (pin "D+") (pinfunction "D+_D+") (pintype "bidirectional"))
    )
    (net (code "46") (name "Net-(R7-Pad1)") (class "Default")
      (node (ref "R7") (pin "1") (pinfunction "1_1") (pintype "passive"))
      (node (ref "X1") (pin "D-") (pinfunction "D-_D-") (pintype "bidirectional"))
    )
    (net (code "47") (name "Net-(S1-P)") (class "Default")
      (node (ref "D10") (pin "C") (pinfunction "C_C") (pintype "passive"))
      (node (ref "S1") (pin "2") (pinfunction "P_2") (pintype "passive"))
    )
    (net (code "48") (name "Net-(U1-AREF)") (class "Default")
      (node (ref "C17") (pin "2") (pinfunction "2_2") (pintype "passive"))
      (node (ref "U1") (pin "42") (pinfunction "AREF_42") (pintype "bidirectional"))
    )
    (net (code "49") (name "Net-(U1-PE2(~{HWB}))") (class "Default")
      (node (ref "R2") (pin "1") (pinfunction "1_1") (pintype "passive"))
      (node (ref "U1") (pin "33") (pinfunction "PE2(~{HWB})_33") (pintype "bidirectional"))
    )
    (net (code "50") (name "Net-(U1-UCAP)") (class "Default")
      (node (ref "C16") (pin "2") (pinfunction "2_2") (pintype "passive"))
      (node (ref "U1") (pin "6") (pinfunction "UCAP_6") (pintype "bidirectional"))
    )
    (net (code "51") (name "unconnected-(C1-P-Pad1)") (class "Default")
      (node (ref "C1") (pin "1") (pinfunction "P_1") (pintype "passive"))
    )
    (net (code "52") (name "unconnected-(C2-P-Pad1)") (class "Default")
      (node (ref "C2") (pin "1") (pinfunction "P_1") (pintype "passive"))
    )
    (net (code "53") (name "unconnected-(C3-P-Pad1)") (class "Default")
      (node (ref "C3") (pin "1") (pinfunction "P_1") (pintype "passive"))
    )
    (net (code "54") (name "unconnected-(C4-P-Pad1)") (class "Default")
      (node (ref "C4") (pin "1") (pinfunction "P_1") (pintype "passive"))
    )
    (net (code "55") (name "unconnected-(EXT1-Pad3)") (class "Default")
      (node (ref "EXT1") (pin "3") (pinfunction "3_3") (pintype "passive"))
    )
    (net (code "56") (name "unconnected-(EXT1-Pad4)") (class "Default")
      (node (ref "EXT1") (pin "4") (pinfunction "4_4") (pintype "passive"))
    )
    (net (code "57") (name "unconnected-(EXT1-Pad5)") (class "Default")
      (node (ref "EXT1") (pin "5") (pinfunction "5_5") (pintype "passive"))
    )
    (net (code "58") (name "unconnected-(EXT1-Pad6)") (class "Default")
      (node (ref "EXT1") (pin "6") (pinfunction "6_6") (pintype "passive"))
    )
    (net (code "59") (name "unconnected-(EXT2-Pad3)") (class "Default")
      (node (ref "EXT2") (pin "3") (pinfunction "3_3") (pintype "passive"))
    )
    (net (code "60") (name "unconnected-(EXT2-Pad4)") (class "Default")
      (node (ref "EXT2") (pin "4") (pinfunction "4_4") (pintype "passive"))
    )
    (net (code "61") (name "unconnected-(J1-Pad2)") (class "Default")
      (node (ref "J1") (pin "2") (pinfunction "2_2") (pintype "passive"))
    )
    (net (code "62") (name "unconnected-(LCD1-IO1-Pad4)") (class "Default")
      (node (ref "LCD1") (pin "4") (pinfunction "IO1_4") (pintype "input"))
    )
    (net (code "63") (name "unconnected-(LCD1-IO2-Pad2)") (class "Default")
      (node (ref "LCD1") (pin "2") (pinfunction "IO2_2") (pintype "output"))
    )
    (net (code "64") (name "unconnected-(O5-P-Pad1)") (class "Default")
      (node (ref "O5") (pin "1") (pinfunction "P_1") (pintype "passive"))
    )
    (net (code "65") (name "unconnected-(O6-P-Pad1)") (class "Default")
      (node (ref "O6") (pin "1") (pinfunction "P_1") (pintype "passive"))
    )
    (net (code "66") (name "unconnected-(O7-P-Pad1)") (class "Default")
      (node (ref "O7") (pin "1") (pinfunction "P_1") (pintype "passive"))
    )
    (net (code "67") (name "unconnected-(O8-P-Pad1)") (class "Default")
      (node (ref "O8") (pin "1") (pinfunction "P_1") (pintype "passive"))
    )
    (net (code "68") (name "unconnected-(S1-O-Pad1)") (class "Default")
      (node (ref "S1") (pin "1") (pinfunction "O_1") (pintype "passive"))
    )
    (net (code "69") (name "unconnected-(U1-PC6(OC3A{slash}~{OC4A})-Pad31)") (class "Default")
      (node (ref "U1") (pin "31") (pinfunction "PC6(OC3A/~{OC4A})_31") (pintype "bidirectional"))
    )
    (net (code "70") (name "unconnected-(U1-PE6(INT.6{slash}AIN0)-Pad1)") (class "Default")
      (node (ref "U1") (pin "1") (pinfunction "PE6(INT.6/AIN0)_1") (pintype "bidirectional"))
    )
    (net (code "71") (name "unconnected-(U2-NC-Pad3)") (class "Default")
      (node (ref "U2") (pin "3") (pinfunction "NC_3") (pintype "bidirectional"))
    )
    (net (code "72") (name "unconnected-(U2-NC-Pad18)") (class "Default")
      (node (ref "U2") (pin "18") (pinfunction "NC_18") (pintype "bidirectional"))
    )
    (net (code "73") (name "unconnected-(X1-PadID)") (class "Default")
      (node (ref "X1") (pin "ID") (pinfunction "ID_ID") (pintype "bidirectional"))
    )
  )
)
